# Schematic_ESP8266_SensorBoard_With_Batte.net
KiCad netlist of a schematic drawn in EasyEDA
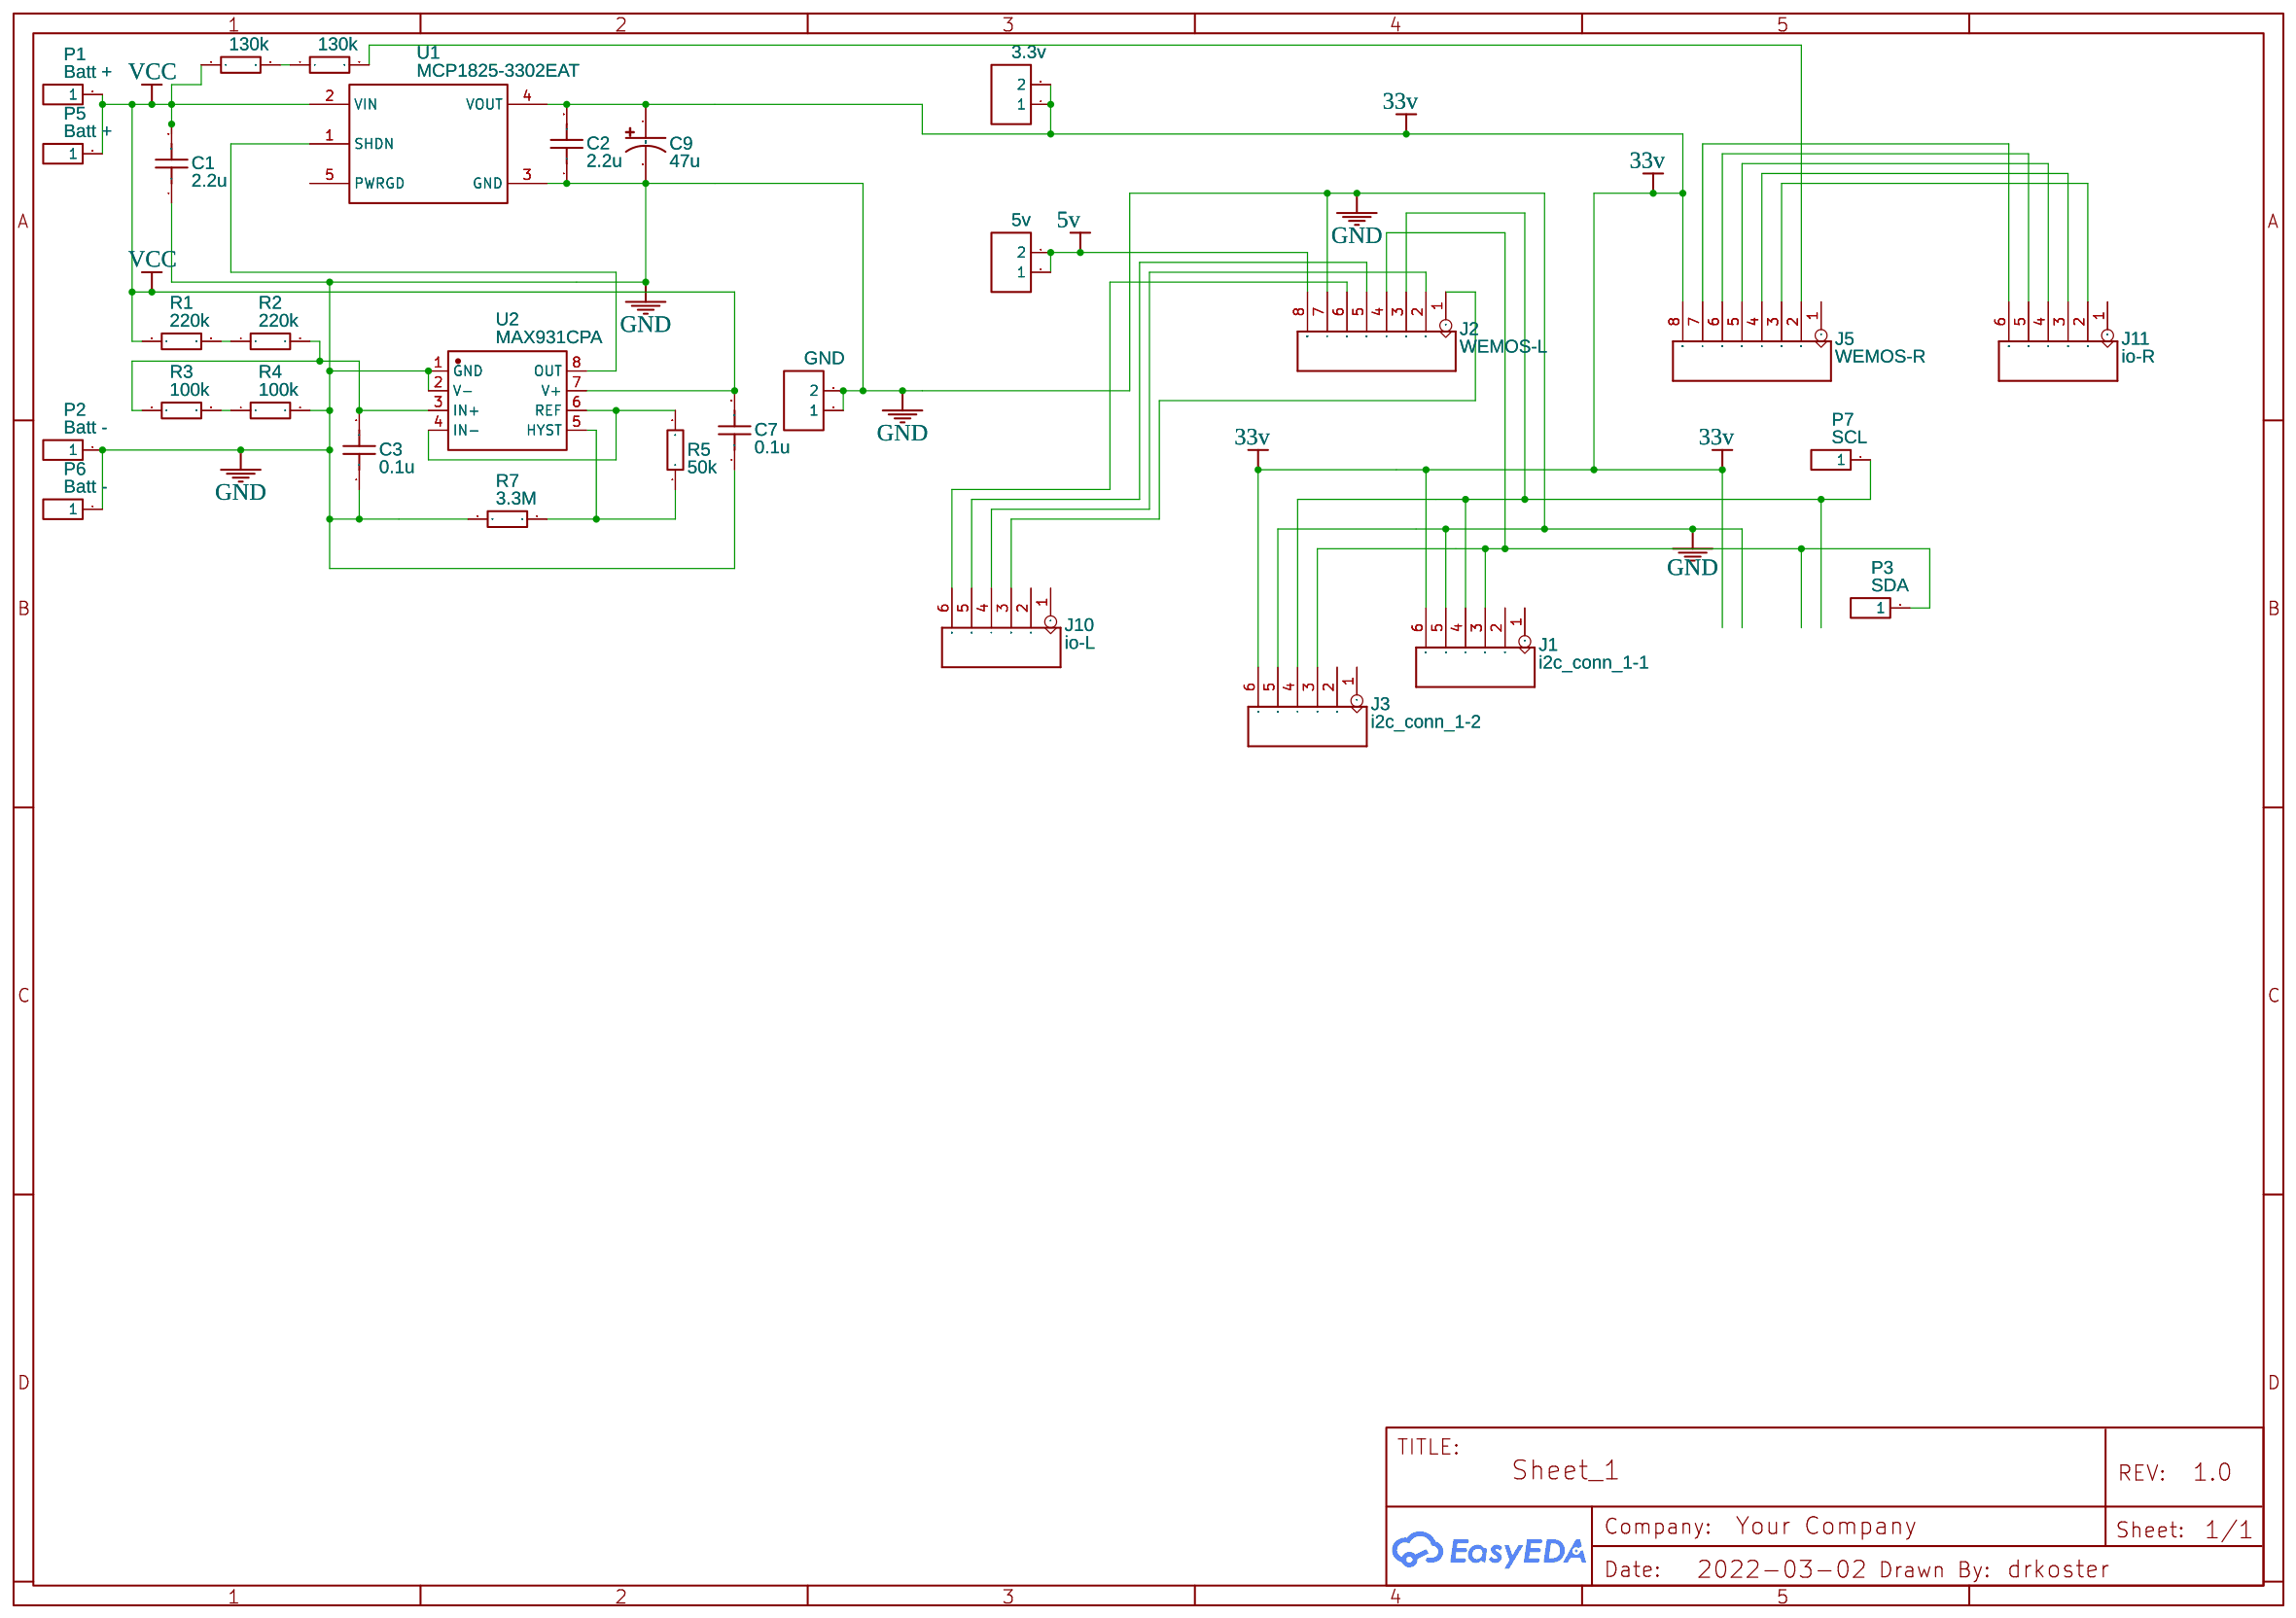
[diagram p0: schematic sheet]

(export (version "E")
  (design (tool "Eeschema 10.0.6"))
  (components
    (comp (ref "C1")
      (value "2.2u")
      (fields (field (name "BOM_Manufacturer Part") "?"))
      (libsource (lib "") (part "Cap_RAD-0.1_US"))
    )
    (comp (ref "C2")
      (value "2.2u")
      (fields (field (name "BOM_Manufacturer Part") "?"))
      (libsource (lib "") (part "Cap_RAD-0.1_US"))
    )
    (comp (ref "C3")
      (value "0.1u")
      (fields (field (name "BOM_Manufacturer Part") "?"))
      (libsource (lib "") (part "Cap_RAD-0.1_US"))
    )
    (comp (ref "C7")
      (value "0.1u")
      (fields (field (name "BOM_Manufacturer Part") "?"))
      (libsource (lib "") (part "Cap_RAD-0.1_US"))
    )
    (comp (ref "C9")
      (value "47u")
      (fields (field (name "BOM_Manufacturer Part") "?"))
      (libsource (lib "") (part "Cap_Electrolytic(TH)_D3.0XF1.5_US"))
    )
    (comp (ref "H1")
      (value "3.3v")
      (fields (field (name "BOM_Supplier Part") "C49661"))
      (libsource (lib "") (part "HDR-F-2.54_1x2"))
    )
    (comp (ref "H2")
      (value "5v")
      (fields (field (name "BOM_Supplier Part") "C49661"))
      (libsource (lib "") (part "HDR-F-2.54_1x2"))
    )
    (comp (ref "H3")
      (value "GND")
      (fields (field (name "BOM_Supplier Part") "C49661"))
      (libsource (lib "") (part "HDR-F-2.54_1x2"))
    )
    (comp (ref "J1")
      (value "i2c_conn_1-1")
      (fields (field (name "BOM_Manufacturer Part") "F185-1106A1BSYA1"))
      (libsource (lib "") (part "Unknown_740_-485"))
    )
    (comp (ref "J2")
      (value "WEMOS-L")
      (fields (field (name "BOM_Manufacturer Part") "F185-1108A0BSYA5"))
      (libsource (lib "") (part "Unknown_690_-645"))
    )
    (comp (ref "J3")
      (value "i2c_conn_1-2")
      (fields (field (name "BOM_Manufacturer Part") "F185-1106A1BSYA1"))
      (libsource (lib "") (part "Unknown_655_-455"))
    )
    (comp (ref "J5")
      (value "WEMOS-R")
      (fields (field (name "BOM_Manufacturer Part") "F185-1108A0BSYA5"))
      (libsource (lib "") (part "Unknown_880_-640"))
    )
    (comp (ref "J10")
      (value "io-L")
      (fields (field (name "BOM_Manufacturer Part") "F185-1106A1BSYA1"))
      (libsource (lib "") (part "Unknown_500_-495"))
    )
    (comp (ref "J11")
      (value "io-R")
      (fields (field (name "BOM_Manufacturer Part") "F185-1106A1BSYA1"))
      (libsource (lib "") (part "Unknown_1035_-640"))
    )
    (comp (ref "P1")
      (value "Batt +")
      (fields
        (field (name "BOM_Manufacturer Part") "Header-Male-2.54_1x1")
        (field (name "BOM_Supplier Part") "C81276")
      )
      (libsource (lib "") (part "Unknown_30_-765"))
    )
    (comp (ref "P2")
      (value "Batt -")
      (fields
        (field (name "BOM_Manufacturer Part") "Header-Male-2.54_1x1")
        (field (name "BOM_Supplier Part") "C81276")
      )
      (libsource (lib "") (part "Unknown_30_-585"))
    )
    (comp (ref "P3")
      (value "SDA")
      (fields
        (field (name "BOM_Manufacturer Part") "Header-Male-2.54_1x1")
        (field (name "BOM_Supplier Part") "C81276")
      )
      (libsource (lib "") (part "Unknown_945_-505"))
    )
    (comp (ref "P5")
      (value "Batt +")
      (fields
        (field (name "BOM_Manufacturer Part") "Header-Male-2.54_1x1")
        (field (name "BOM_Supplier Part") "C81276")
      )
      (libsource (lib "") (part "Unknown_30_-735"))
    )
    (comp (ref "P6")
      (value "Batt -")
      (fields
        (field (name "BOM_Manufacturer Part") "Header-Male-2.54_1x1")
        (field (name "BOM_Supplier Part") "C81276")
      )
      (libsource (lib "") (part "Unknown_30_-555"))
    )
    (comp (ref "P7")
      (value "SCL")
      (fields
        (field (name "BOM_Manufacturer Part") "Header-Male-2.54_1x1")
        (field (name "BOM_Supplier Part") "C81276")
      )
      (libsource (lib "") (part "Unknown_925_-580"))
    )
    (comp (ref "R1")
      (value "220k")
      (fields
        (field (name "BOM_Manufacturer Part") "MF1W-5.1Ω±1%")
        (field (name "BOM_Supplier Part") "C127239")
      )
      (libsource (lib "") (part "MF1W-5.1Ω±1%_1"))
    )
    (comp (ref "R2")
      (value "220k")
      (fields
        (field (name "BOM_Manufacturer Part") "MF1W-5.1Ω±1%")
        (field (name "BOM_Supplier Part") "C127239")
      )
      (libsource (lib "") (part "MF1W-5.1Ω±1%_1"))
    )
    (comp (ref "R3")
      (value "100k")
      (fields
        (field (name "BOM_Manufacturer Part") "MF1W-5.1Ω±1%")
        (field (name "BOM_Supplier Part") "C127239")
      )
      (libsource (lib "") (part "MF1W-5.1Ω±1%_1"))
    )
    (comp (ref "R4")
      (value "100k")
      (fields
        (field (name "BOM_Manufacturer Part") "MF1W-5.1Ω±1%")
        (field (name "BOM_Supplier Part") "C127239")
      )
      (libsource (lib "") (part "MF1W-5.1Ω±1%_1"))
    )
    (comp (ref "R5")
      (value "50k")
      (fields
        (field (name "BOM_Manufacturer Part") "MF1W-5.1Ω±1%")
        (field (name "BOM_Supplier Part") "C127239")
      )
      (libsource (lib "") (part "MF1W-5.1Ω±1%"))
    )
    (comp (ref "R6")
      (value "130k")
      (fields
        (field (name "BOM_Manufacturer Part") "MF1W-5.1Ω±1%")
        (field (name "BOM_Supplier Part") "C127239")
      )
      (libsource (lib "") (part "MF1W-5.1Ω±1%_1"))
    )
    (comp (ref "R7")
      (value "3.3M")
      (fields
        (field (name "BOM_Manufacturer Part") "MF1W-5.1Ω±1%")
        (field (name "BOM_Supplier Part") "C127239")
      )
      (libsource (lib "") (part "MF1W-5.1Ω±1%_2"))
    )
    (comp (ref "R8")
      (value "130k")
      (fields
        (field (name "BOM_Manufacturer Part") "MF1W-5.1Ω±1%")
        (field (name "BOM_Supplier Part") "C127239")
      )
      (libsource (lib "") (part "MF1W-5.1Ω±1%_1"))
    )
    (comp (ref "U1") (value "MCP1825-3302EAT") (libsource (lib "") (part "MCP1825-3302EAT")))
    (comp (ref "U2")
      (value "MAX931CPA")
      (fields (field (name "BOM_Supplier Part") "700-MAX931CPA"))
      (libsource (lib "") (part "MAX931CPA-DIP8"))
    )
  )
  (nets
    (net (code "1") (name "5v") (class "Default")
      (node (ref "H2") (pin "1") (pinfunction "1_1") (pintype "input"))
      (node (ref "H2") (pin "2") (pinfunction "2_2") (pintype "input"))
      (node (ref "J2") (pin "8") (pinfunction "8_8") (pintype "unspecified"))
    )
    (net (code "2") (name "33v") (class "Default")
      (node (ref "C2") (pin "2") (pinfunction "2_2") (pintype "unspecified"))
      (node (ref "C9") (pin "1") (pinfunction "1_1") (pintype "unspecified"))
      (node (ref "H1") (pin "1") (pinfunction "1_1") (pintype "input"))
      (node (ref "H1") (pin "2") (pinfunction "2_2") (pintype "input"))
      (node (ref "J1") (pin "6") (pinfunction "6_6") (pintype "unspecified"))
      (node (ref "J3") (pin "6") (pinfunction "6_6") (pintype "unspecified"))
      (node (ref "J5") (pin "8") (pinfunction "8_8") (pintype "unspecified"))
      (node (ref "U1") (pin "4") (pinfunction "VOUT_4") (pintype "passive"))
    )
    (net (code "3") (name "GND") (class "Default")
      (node (ref "C1") (pin "1") (pinfunction "1_1") (pintype "unspecified"))
      (node (ref "C2") (pin "1") (pinfunction "1_1") (pintype "unspecified"))
      (node (ref "C3") (pin "1") (pinfunction "1_1") (pintype "unspecified"))
      (node (ref "C7") (pin "1") (pinfunction "1_1") (pintype "unspecified"))
      (node (ref "C9") (pin "2") (pinfunction "2_2") (pintype "unspecified"))
      (node (ref "H3") (pin "1") (pinfunction "1_1") (pintype "input"))
      (node (ref "H3") (pin "2") (pinfunction "2_2") (pintype "input"))
      (node (ref "J1") (pin "5") (pinfunction "5_5") (pintype "unspecified"))
      (node (ref "J2") (pin "7") (pinfunction "7_7") (pintype "unspecified"))
      (node (ref "J3") (pin "5") (pinfunction "5_5") (pintype "unspecified"))
      (node (ref "P2") (pin "1") (pinfunction "1_1") (pintype "input"))
      (node (ref "P6") (pin "1") (pinfunction "1_1") (pintype "input"))
      (node (ref "R4") (pin "2") (pinfunction "2_2") (pintype "input"))
      (node (ref "R7") (pin "2") (pinfunction "2_2") (pintype "input"))
      (node (ref "U1") (pin "3") (pinfunction "GND_3") (pintype "passive"))
      (node (ref "U2") (pin "1") (pinfunction "GND_1") (pintype "unspecified"))
      (node (ref "U2") (pin "2") (pinfunction "V-_2") (pintype "unspecified"))
    )
    (net (code "4") (name "Net-(J1-Pad3)") (class "Default")
      (node (ref "J1") (pin "3") (pinfunction "3_3") (pintype "unspecified"))
      (node (ref "J2") (pin "4") (pinfunction "4_4") (pintype "unspecified"))
      (node (ref "J3") (pin "3") (pinfunction "3_3") (pintype "unspecified"))
      (node (ref "P3") (pin "1") (pinfunction "1_1") (pintype "input"))
    )
    (net (code "5") (name "Net-(J1-Pad4)") (class "Default")
      (node (ref "J1") (pin "4") (pinfunction "4_4") (pintype "unspecified"))
      (node (ref "J2") (pin "3") (pinfunction "3_3") (pintype "unspecified"))
      (node (ref "J3") (pin "4") (pinfunction "4_4") (pintype "unspecified"))
      (node (ref "P7") (pin "1") (pinfunction "1_1") (pintype "input"))
    )
    (net (code "6") (name "Net-(J5-Pad2)") (class "Default")
      (node (ref "J5") (pin "2") (pinfunction "2_2") (pintype "unspecified"))
      (node (ref "R8") (pin "2") (pinfunction "2_2") (pintype "input"))
    )
    (net (code "7") (name "Net-(J10-Pad3)") (class "Default")
      (node (ref "J10") (pin "3") (pinfunction "3_3") (pintype "unspecified"))
      (node (ref "J2") (pin "1") (pinfunction "1_1") (pintype "unspecified"))
    )
    (net (code "8") (name "Net-(J10-Pad4)") (class "Default")
      (node (ref "J10") (pin "4") (pinfunction "4_4") (pintype "unspecified"))
      (node (ref "J2") (pin "2") (pinfunction "2_2") (pintype "unspecified"))
    )
    (net (code "9") (name "Net-(J10-Pad5)") (class "Default")
      (node (ref "J10") (pin "5") (pinfunction "5_5") (pintype "unspecified"))
      (node (ref "J2") (pin "5") (pinfunction "5_5") (pintype "unspecified"))
    )
    (net (code "10") (name "Net-(J10-Pad6)") (class "Default")
      (node (ref "J10") (pin "6") (pinfunction "6_6") (pintype "unspecified"))
      (node (ref "J2") (pin "6") (pinfunction "6_6") (pintype "unspecified"))
    )
    (net (code "11") (name "Net-(J11-Pad2)") (class "Default")
      (node (ref "J11") (pin "2") (pinfunction "2_2") (pintype "unspecified"))
      (node (ref "J5") (pin "3") (pinfunction "3_3") (pintype "unspecified"))
    )
    (net (code "12") (name "Net-(J11-Pad3)") (class "Default")
      (node (ref "J11") (pin "3") (pinfunction "3_3") (pintype "unspecified"))
      (node (ref "J5") (pin "4") (pinfunction "4_4") (pintype "unspecified"))
    )
    (net (code "13") (name "Net-(J11-Pad4)") (class "Default")
      (node (ref "J11") (pin "4") (pinfunction "4_4") (pintype "unspecified"))
      (node (ref "J5") (pin "5") (pinfunction "5_5") (pintype "unspecified"))
    )
    (net (code "14") (name "Net-(J11-Pad5)") (class "Default")
      (node (ref "J11") (pin "5") (pinfunction "5_5") (pintype "unspecified"))
      (node (ref "J5") (pin "6") (pinfunction "6_6") (pintype "unspecified"))
    )
    (net (code "15") (name "Net-(J11-Pad6)") (class "Default")
      (node (ref "J11") (pin "6") (pinfunction "6_6") (pintype "unspecified"))
      (node (ref "J5") (pin "7") (pinfunction "7_7") (pintype "unspecified"))
    )
    (net (code "16") (name "Net-(R1-Pad2)") (class "Default")
      (node (ref "R1") (pin "2") (pinfunction "2_2") (pintype "input"))
      (node (ref "R2") (pin "1") (pinfunction "1_1") (pintype "input"))
    )
    (net (code "17") (name "Net-(R3-Pad2)") (class "Default")
      (node (ref "R3") (pin "2") (pinfunction "2_2") (pintype "input"))
      (node (ref "R4") (pin "1") (pinfunction "1_1") (pintype "input"))
    )
    (net (code "18") (name "Net-(R6-Pad2)") (class "Default")
      (node (ref "R6") (pin "2") (pinfunction "2_2") (pintype "input"))
      (node (ref "R8") (pin "1") (pinfunction "1_1") (pintype "input"))
    )
    (net (code "19") (name "Net-(U1-SHDN)") (class "Default")
      (node (ref "U1") (pin "1") (pinfunction "SHDN_1") (pintype "unspecified"))
      (node (ref "U2") (pin "8") (pinfunction "OUT_8") (pintype "unspecified"))
    )
    (net (code "20") (name "Net-(U2-HYST)") (class "Default")
      (node (ref "R5") (pin "1") (pinfunction "1_1") (pintype "input"))
      (node (ref "R7") (pin "1") (pinfunction "1_1") (pintype "input"))
      (node (ref "U2") (pin "5") (pinfunction "HYST_5") (pintype "unspecified"))
    )
    (net (code "21") (name "Net-(U2-IN+)") (class "Default")
      (node (ref "C3") (pin "2") (pinfunction "2_2") (pintype "unspecified"))
      (node (ref "R2") (pin "2") (pinfunction "2_2") (pintype "input"))
      (node (ref "R3") (pin "1") (pinfunction "1_1") (pintype "input"))
      (node (ref "U2") (pin "3") (pinfunction "IN+_3") (pintype "unspecified"))
    )
    (net (code "22") (name "Net-(U2-IN-)") (class "Default")
      (node (ref "R5") (pin "2") (pinfunction "2_2") (pintype "input"))
      (node (ref "U2") (pin "4") (pinfunction "IN-_4") (pintype "unspecified"))
      (node (ref "U2") (pin "6") (pinfunction "REF_6") (pintype "unspecified"))
    )
    (net (code "23") (name "VCC") (class "Default")
      (node (ref "C1") (pin "2") (pinfunction "2_2") (pintype "unspecified"))
      (node (ref "C7") (pin "2") (pinfunction "2_2") (pintype "unspecified"))
      (node (ref "P1") (pin "1") (pinfunction "1_1") (pintype "input"))
      (node (ref "P5") (pin "1") (pinfunction "1_1") (pintype "input"))
      (node (ref "R1") (pin "1") (pinfunction "1_1") (pintype "input"))
      (node (ref "R6") (pin "1") (pinfunction "1_1") (pintype "input"))
      (node (ref "U1") (pin "2") (pinfunction "VIN_2") (pintype "passive"))
      (node (ref "U2") (pin "7") (pinfunction "V+_7") (pintype "unspecified"))
    )
    (net (code "24") (name "unconnected-(J1-Pad1)") (class "Default")
      (node (ref "J1") (pin "1") (pinfunction "1_1") (pintype "unspecified"))
    )
    (net (code "25") (name "unconnected-(J1-Pad2)") (class "Default")
      (node (ref "J1") (pin "2") (pinfunction "2_2") (pintype "unspecified"))
    )
    (net (code "26") (name "unconnected-(J3-Pad1)") (class "Default")
      (node (ref "J3") (pin "1") (pinfunction "1_1") (pintype "unspecified"))
    )
    (net (code "27") (name "unconnected-(J3-Pad2)") (class "Default")
      (node (ref "J3") (pin "2") (pinfunction "2_2") (pintype "unspecified"))
    )
    (net (code "28") (name "unconnected-(J5-Pad1)") (class "Default")
      (node (ref "J5") (pin "1") (pinfunction "1_1") (pintype "unspecified"))
    )
    (net (code "29") (name "unconnected-(J10-Pad1)") (class "Default")
      (node (ref "J10") (pin "1") (pinfunction "1_1") (pintype "unspecified"))
    )
    (net (code "30") (name "unconnected-(J10-Pad2)") (class "Default")
      (node (ref "J10") (pin "2") (pinfunction "2_2") (pintype "unspecified"))
    )
    (net (code "31") (name "unconnected-(J11-Pad1)") (class "Default")
      (node (ref "J11") (pin "1") (pinfunction "1_1") (pintype "unspecified"))
    )
    (net (code "32") (name "unconnected-(U1-PWRGD-Pad5)") (class "Default")
      (node (ref "U1") (pin "5") (pinfunction "PWRGD_5") (pintype "passive"))
    )
  )
)
